# calculator4.net
KiCad netlist of a schematic drawn in EAGLE
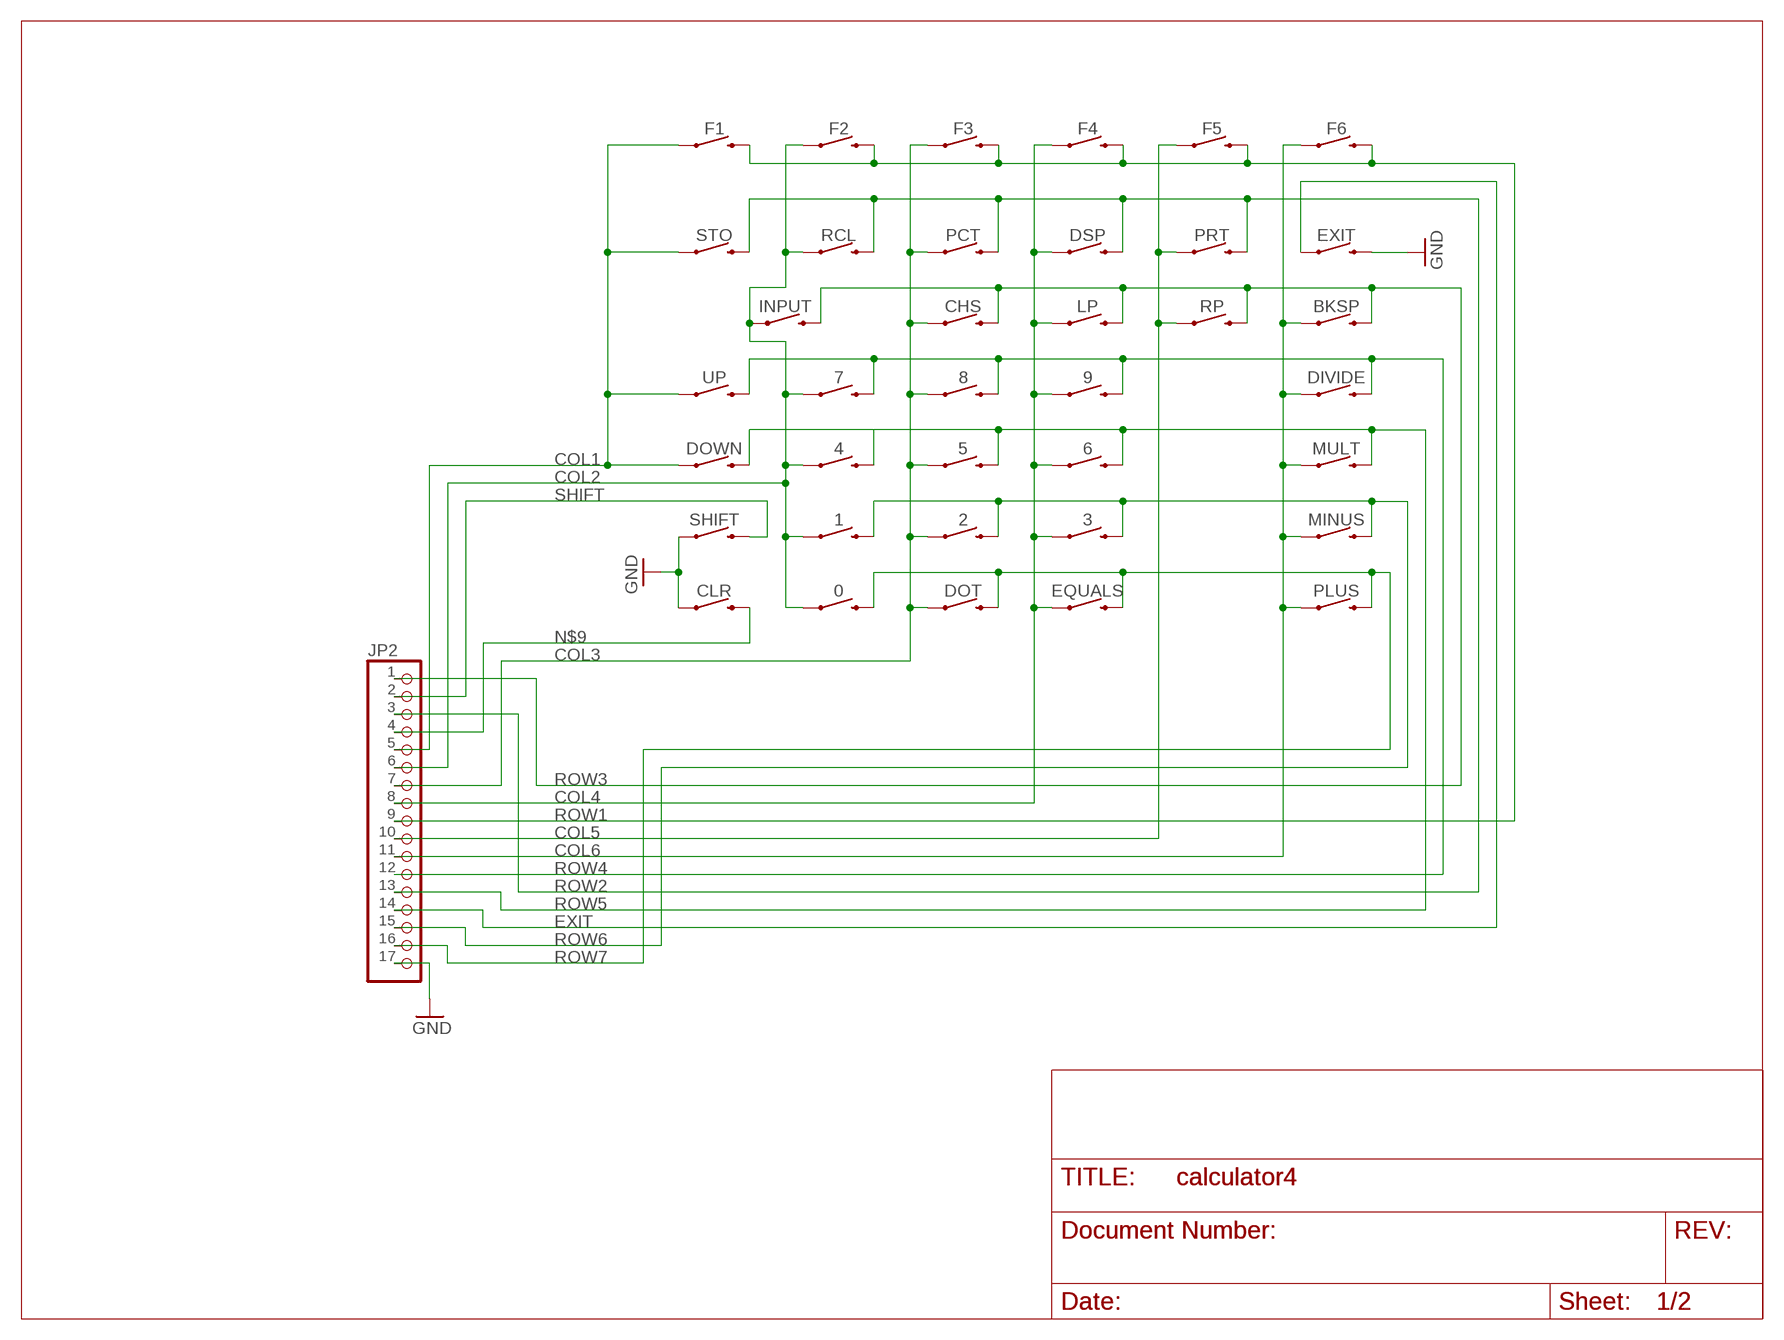
[diagram p0: schematic, sheet 1]
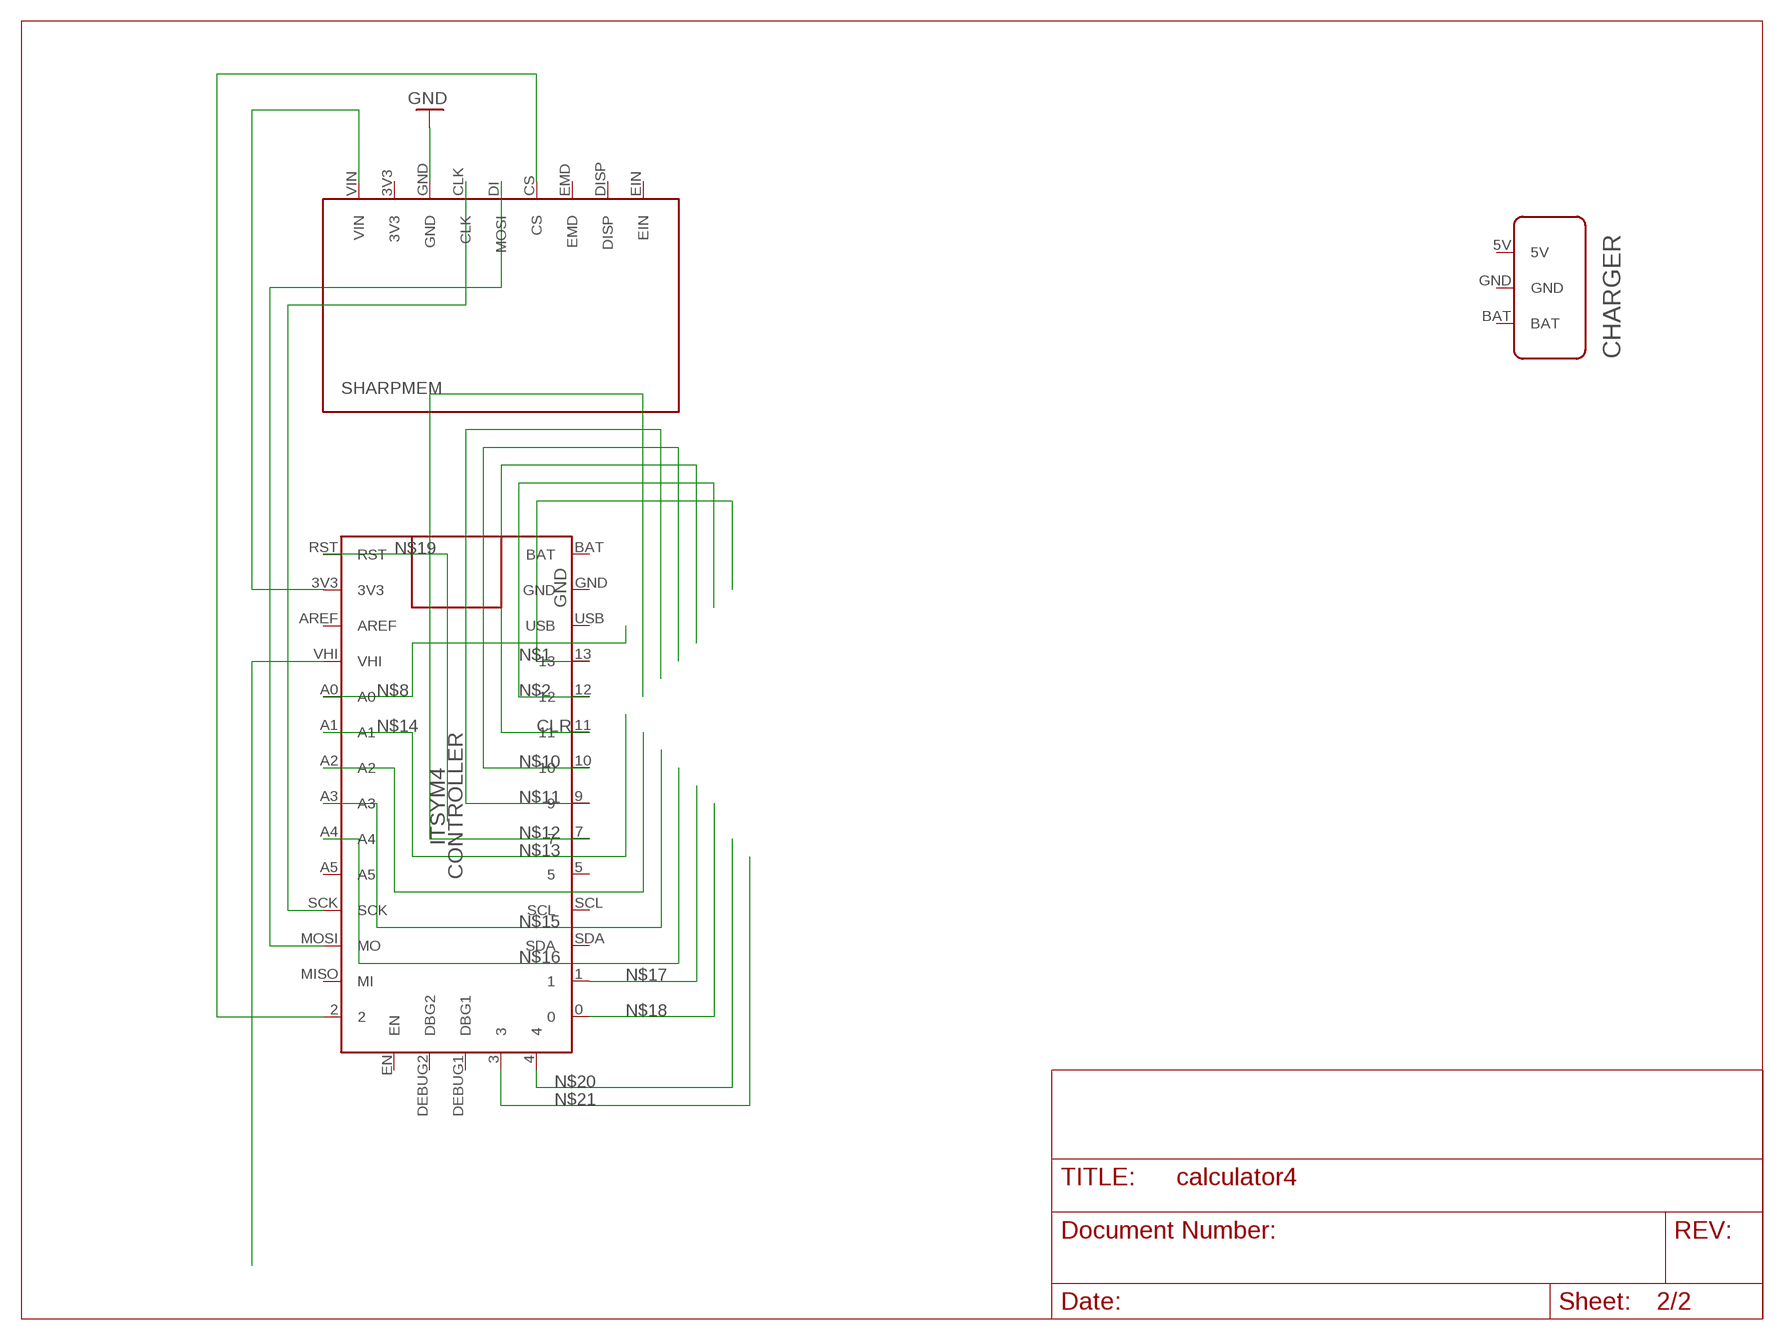
[diagram p1: schematic, sheet 2]

(export (version "E")
  (design (tool "Eeschema 10.0.6"))
  (components
    (comp (ref "0")
      (value "BUTTON")
      (footprint "eagle-import:BUTTON")
      (libsource (lib "eagle-import") (part "BUTTON"))
    )
    (comp (ref "1")
      (value "BUTTON")
      (footprint "eagle-import:BUTTON")
      (libsource (lib "eagle-import") (part "BUTTON"))
    )
    (comp (ref "2")
      (value "BUTTON")
      (footprint "eagle-import:BUTTON")
      (libsource (lib "eagle-import") (part "BUTTON"))
    )
    (comp (ref "3")
      (value "BUTTON")
      (footprint "eagle-import:BUTTON")
      (libsource (lib "eagle-import") (part "BUTTON"))
    )
    (comp (ref "4")
      (value "BUTTON")
      (footprint "eagle-import:BUTTON")
      (libsource (lib "eagle-import") (part "BUTTON"))
    )
    (comp (ref "5")
      (value "BUTTON")
      (footprint "eagle-import:BUTTON")
      (libsource (lib "eagle-import") (part "BUTTON"))
    )
    (comp (ref "6")
      (value "BUTTON")
      (footprint "eagle-import:BUTTON")
      (libsource (lib "eagle-import") (part "BUTTON"))
    )
    (comp (ref "7")
      (value "BUTTON")
      (footprint "eagle-import:BUTTON")
      (libsource (lib "eagle-import") (part "BUTTON"))
    )
    (comp (ref "8")
      (value "BUTTON")
      (footprint "eagle-import:BUTTON")
      (libsource (lib "eagle-import") (part "BUTTON"))
    )
    (comp (ref "9")
      (value "BUTTON")
      (footprint "eagle-import:BUTTON")
      (libsource (lib "eagle-import") (part "BUTTON"))
    )
    (comp (ref "BKSP")
      (value "BUTTON")
      (footprint "eagle-import:BUTTON")
      (libsource (lib "eagle-import") (part "BUTTON"))
    )
    (comp (ref "CHS")
      (value "BUTTON")
      (footprint "eagle-import:BUTTON")
      (libsource (lib "eagle-import") (part "BUTTON"))
    )
    (comp (ref "CLR")
      (value "BUTTON")
      (footprint "eagle-import:BUTTON")
      (libsource (lib "eagle-import") (part "BUTTON"))
    )
    (comp (ref "DIVIDE")
      (value "BUTTON")
      (footprint "eagle-import:BUTTON")
      (libsource (lib "eagle-import") (part "BUTTON"))
    )
    (comp (ref "DOT")
      (value "BUTTON")
      (footprint "eagle-import:BUTTON")
      (libsource (lib "eagle-import") (part "BUTTON"))
    )
    (comp (ref "DOWN")
      (value "BUTTON")
      (footprint "eagle-import:BUTTON")
      (libsource (lib "eagle-import") (part "BUTTON"))
    )
    (comp (ref "DSP")
      (value "BUTTON")
      (footprint "eagle-import:BUTTON")
      (libsource (lib "eagle-import") (part "BUTTON"))
    )
    (comp (ref "EQUALS")
      (value "BUTTON")
      (footprint "eagle-import:BUTTON")
      (libsource (lib "eagle-import") (part "BUTTON"))
    )
    (comp (ref "EXIT")
      (value "BUTTON")
      (footprint "eagle-import:BUTTON")
      (libsource (lib "eagle-import") (part "BUTTON"))
    )
    (comp (ref "F1")
      (value "BUTTON")
      (footprint "eagle-import:BUTTON")
      (libsource (lib "eagle-import") (part "BUTTON"))
    )
    (comp (ref "F2")
      (value "BUTTON")
      (footprint "eagle-import:BUTTON")
      (libsource (lib "eagle-import") (part "BUTTON"))
    )
    (comp (ref "F3")
      (value "BUTTON")
      (footprint "eagle-import:BUTTON")
      (libsource (lib "eagle-import") (part "BUTTON"))
    )
    (comp (ref "F4")
      (value "BUTTON")
      (footprint "eagle-import:BUTTON")
      (libsource (lib "eagle-import") (part "BUTTON"))
    )
    (comp (ref "F5")
      (value "BUTTON")
      (footprint "eagle-import:BUTTON")
      (libsource (lib "eagle-import") (part "BUTTON"))
    )
    (comp (ref "F6")
      (value "BUTTON")
      (footprint "eagle-import:BUTTON")
      (libsource (lib "eagle-import") (part "BUTTON"))
    )
    (comp (ref "INPUT")
      (value "BUTTON")
      (footprint "eagle-import:BUTTON")
      (libsource (lib "eagle-import") (part "BUTTON"))
    )
    (comp (ref "JP2")
      (value "PINHD-1X17/90")
      (footprint "eagle-import:1X17_90")
      (libsource (lib "eagle-import") (part "PINHD-1X17/90"))
    )
    (comp (ref "LP")
      (value "BUTTON")
      (footprint "eagle-import:BUTTON")
      (libsource (lib "eagle-import") (part "BUTTON"))
    )
    (comp (ref "MINUS")
      (value "BUTTON")
      (footprint "eagle-import:BUTTON")
      (libsource (lib "eagle-import") (part "BUTTON"))
    )
    (comp (ref "MULT")
      (value "BUTTON")
      (footprint "eagle-import:BUTTON")
      (libsource (lib "eagle-import") (part "BUTTON"))
    )
    (comp (ref "PCT")
      (value "BUTTON")
      (footprint "eagle-import:BUTTON")
      (libsource (lib "eagle-import") (part "BUTTON"))
    )
    (comp (ref "PLUS")
      (value "BUTTON")
      (footprint "eagle-import:BUTTON")
      (libsource (lib "eagle-import") (part "BUTTON"))
    )
    (comp (ref "PRT")
      (value "BUTTON")
      (footprint "eagle-import:BUTTON")
      (libsource (lib "eagle-import") (part "BUTTON"))
    )
    (comp (ref "RCL")
      (value "BUTTON")
      (footprint "eagle-import:BUTTON")
      (libsource (lib "eagle-import") (part "BUTTON"))
    )
    (comp (ref "RP")
      (value "BUTTON")
      (footprint "eagle-import:BUTTON")
      (libsource (lib "eagle-import") (part "BUTTON"))
    )
    (comp (ref "SHIFT")
      (value "BUTTON")
      (footprint "eagle-import:BUTTON")
      (libsource (lib "eagle-import") (part "BUTTON"))
    )
    (comp (ref "STO")
      (value "BUTTON")
      (footprint "eagle-import:BUTTON")
      (libsource (lib "eagle-import") (part "BUTTON"))
    )
    (comp (ref "UP")
      (value "BUTTON")
      (footprint "eagle-import:BUTTON")
      (libsource (lib "eagle-import") (part "BUTTON"))
    )
    (comp (ref "CHARGER")
      (value "LIPO_BACKPACK")
      (footprint "eagle-import:LIPO_BACKPACK")
      (libsource (lib "eagle-import") (part "LIPO_BACKPACK"))
    )
    (comp (ref "CONTROLLER")
      (value "ITSYM4")
      (footprint "eagle-import:ITSYM4")
      (libsource (lib "eagle-import") (part "ITSYM4"))
    )
    (comp (ref "SHARPMEM")
      (value "SHARPMEM")
      (footprint "eagle-import:SHARPMEM")
      (libsource (lib "eagle-import") (part "SHARPMEM"))
    )
  )
  (nets
    (net (code "1") (name "CLR") (class "Default")
      (node (ref "CONTROLLER") (pin "11") (pinfunction "11_11") (pintype "bidirectional"))
    )
    (net (code "2") (name "COL1") (class "Default")
      (node (ref "DOWN") (pin "1") (pinfunction "1_1") (pintype "passive"))
      (node (ref "F1") (pin "1") (pinfunction "1_1") (pintype "passive"))
      (node (ref "JP2") (pin "5") (pinfunction "5_5") (pintype "passive"))
      (node (ref "STO") (pin "1") (pinfunction "1_1") (pintype "passive"))
      (node (ref "UP") (pin "1") (pinfunction "1_1") (pintype "passive"))
    )
    (net (code "3") (name "COL2") (class "Default")
      (node (ref "0") (pin "1") (pinfunction "1_1") (pintype "passive"))
      (node (ref "1") (pin "1") (pinfunction "1_1") (pintype "passive"))
      (node (ref "4") (pin "1") (pinfunction "1_1") (pintype "passive"))
      (node (ref "7") (pin "1") (pinfunction "1_1") (pintype "passive"))
      (node (ref "F2") (pin "1") (pinfunction "1_1") (pintype "passive"))
      (node (ref "INPUT") (pin "1") (pinfunction "1_1") (pintype "passive"))
      (node (ref "JP2") (pin "6") (pinfunction "6_6") (pintype "passive"))
      (node (ref "RCL") (pin "1") (pinfunction "1_1") (pintype "passive"))
    )
    (net (code "4") (name "COL3") (class "Default")
      (node (ref "2") (pin "1") (pinfunction "1_1") (pintype "passive"))
      (node (ref "5") (pin "1") (pinfunction "1_1") (pintype "passive"))
      (node (ref "8") (pin "1") (pinfunction "1_1") (pintype "passive"))
      (node (ref "CHS") (pin "1") (pinfunction "1_1") (pintype "passive"))
      (node (ref "DOT") (pin "1") (pinfunction "1_1") (pintype "passive"))
      (node (ref "F3") (pin "1") (pinfunction "1_1") (pintype "passive"))
      (node (ref "JP2") (pin "7") (pinfunction "7_7") (pintype "passive"))
      (node (ref "PCT") (pin "1") (pinfunction "1_1") (pintype "passive"))
    )
    (net (code "5") (name "COL4") (class "Default")
      (node (ref "3") (pin "1") (pinfunction "1_1") (pintype "passive"))
      (node (ref "6") (pin "1") (pinfunction "1_1") (pintype "passive"))
      (node (ref "9") (pin "1") (pinfunction "1_1") (pintype "passive"))
      (node (ref "DSP") (pin "1") (pinfunction "1_1") (pintype "passive"))
      (node (ref "EQUALS") (pin "1") (pinfunction "1_1") (pintype "passive"))
      (node (ref "F4") (pin "1") (pinfunction "1_1") (pintype "passive"))
      (node (ref "JP2") (pin "8") (pinfunction "8_8") (pintype "passive"))
      (node (ref "LP") (pin "1") (pinfunction "1_1") (pintype "passive"))
    )
    (net (code "6") (name "COL5") (class "Default")
      (node (ref "F5") (pin "1") (pinfunction "1_1") (pintype "passive"))
      (node (ref "JP2") (pin "10") (pinfunction "10_10") (pintype "passive"))
      (node (ref "PRT") (pin "1") (pinfunction "1_1") (pintype "passive"))
      (node (ref "RP") (pin "1") (pinfunction "1_1") (pintype "passive"))
    )
    (net (code "7") (name "COL6") (class "Default")
      (node (ref "BKSP") (pin "1") (pinfunction "1_1") (pintype "passive"))
      (node (ref "DIVIDE") (pin "1") (pinfunction "1_1") (pintype "passive"))
      (node (ref "F6") (pin "1") (pinfunction "1_1") (pintype "passive"))
      (node (ref "JP2") (pin "11") (pinfunction "11_11") (pintype "passive"))
      (node (ref "MINUS") (pin "1") (pinfunction "1_1") (pintype "passive"))
      (node (ref "MULT") (pin "1") (pinfunction "1_1") (pintype "passive"))
      (node (ref "PLUS") (pin "1") (pinfunction "1_1") (pintype "passive"))
    )
    (net (code "8") (name "EXIT") (class "Default")
      (node (ref "EXIT") (pin "1") (pinfunction "1_1") (pintype "passive"))
      (node (ref "JP2") (pin "14") (pinfunction "14_14") (pintype "passive"))
    )
    (net (code "9") (name "GND") (class "Default")
      (node (ref "CLR") (pin "1") (pinfunction "1_1") (pintype "passive"))
      (node (ref "CONTROLLER") (pin "GND") (pinfunction "GND_GND") (pintype "bidirectional"))
      (node (ref "EXIT") (pin "3") (pinfunction "2_3") (pintype "passive"))
      (node (ref "JP2") (pin "17") (pinfunction "17_17") (pintype "passive"))
      (node (ref "SHARPMEM") (pin "GND") (pinfunction "GND_GND") (pintype "bidirectional"))
      (node (ref "SHIFT") (pin "1") (pinfunction "1_1") (pintype "passive"))
    )
    (net (code "10") (name "N$1") (class "Default")
      (node (ref "CONTROLLER") (pin "13") (pinfunction "13_13") (pintype "bidirectional"))
    )
    (net (code "11") (name "N$2") (class "Default")
      (node (ref "CONTROLLER") (pin "12") (pinfunction "12_12") (pintype "bidirectional"))
    )
    (net (code "12") (name "N$8") (class "Default")
      (node (ref "CONTROLLER") (pin "A0") (pinfunction "A0_A0") (pintype "bidirectional"))
    )
    (net (code "13") (name "N$9") (class "Default")
      (node (ref "CLR") (pin "3") (pinfunction "2_3") (pintype "passive"))
      (node (ref "JP2") (pin "4") (pinfunction "4_4") (pintype "passive"))
    )
    (net (code "14") (name "N$10") (class "Default")
      (node (ref "CONTROLLER") (pin "10") (pinfunction "10_10") (pintype "bidirectional"))
    )
    (net (code "15") (name "N$11") (class "Default")
      (node (ref "CONTROLLER") (pin "9") (pinfunction "9_9") (pintype "bidirectional"))
    )
    (net (code "16") (name "N$12") (class "Default")
      (node (ref "CONTROLLER") (pin "7") (pinfunction "7_7") (pintype "bidirectional"))
    )
    (net (code "17") (name "N$13") (class "Default")
      (node (ref "CONTROLLER") (pin "A1") (pinfunction "A1_A1") (pintype "bidirectional"))
    )
    (net (code "18") (name "N$14") (class "Default")
      (node (ref "CONTROLLER") (pin "A2") (pinfunction "A2_A2") (pintype "bidirectional"))
    )
    (net (code "19") (name "N$15") (class "Default")
      (node (ref "CONTROLLER") (pin "A3") (pinfunction "A3_A3") (pintype "bidirectional"))
    )
    (net (code "20") (name "N$16") (class "Default")
      (node (ref "CONTROLLER") (pin "A4") (pinfunction "A4_A4") (pintype "bidirectional"))
    )
    (net (code "21") (name "N$17") (class "Default")
      (node (ref "CONTROLLER") (pin "1") (pinfunction "1_1") (pintype "bidirectional"))
    )
    (net (code "22") (name "N$18") (class "Default")
      (node (ref "CONTROLLER") (pin "0") (pinfunction "0_0") (pintype "bidirectional"))
    )
    (net (code "23") (name "N$19") (class "Default")
      (node (ref "CONTROLLER") (pin "RST") (pinfunction "RST_RST") (pintype "bidirectional"))
    )
    (net (code "24") (name "N$20") (class "Default")
      (node (ref "CONTROLLER") (pin "4") (pinfunction "4_4") (pintype "bidirectional"))
    )
    (net (code "25") (name "N$21") (class "Default")
      (node (ref "CONTROLLER") (pin "3") (pinfunction "3_3") (pintype "bidirectional"))
    )
    (net (code "26") (name "Net-(CONTROLLER-MO)") (class "Default")
      (node (ref "CONTROLLER") (pin "MOSI") (pinfunction "MO_MOSI") (pintype "bidirectional"))
      (node (ref "SHARPMEM") (pin "DI") (pinfunction "MOSI_DI") (pintype "bidirectional"))
    )
    (net (code "27") (name "Net-(CONTROLLER-Pad2)") (class "Default")
      (node (ref "CONTROLLER") (pin "2") (pinfunction "2_2") (pintype "bidirectional"))
      (node (ref "SHARPMEM") (pin "CS") (pinfunction "CS_CS") (pintype "bidirectional"))
    )
    (net (code "28") (name "Net-(CONTROLLER-Pad3V3)") (class "Default")
      (node (ref "CONTROLLER") (pin "3V3") (pinfunction "3V3_3V3") (pintype "bidirectional"))
      (node (ref "SHARPMEM") (pin "VIN") (pinfunction "VIN_VIN") (pintype "bidirectional"))
    )
    (net (code "29") (name "Net-(CONTROLLER-PadSCK)") (class "Default")
      (node (ref "CONTROLLER") (pin "SCK") (pinfunction "SCK_SCK") (pintype "bidirectional"))
      (node (ref "SHARPMEM") (pin "CLK") (pinfunction "CLK_CLK") (pintype "bidirectional"))
    )
    (net (code "30") (name "ROW1") (class "Default")
      (node (ref "F1") (pin "3") (pinfunction "2_3") (pintype "passive"))
      (node (ref "F2") (pin "3") (pinfunction "2_3") (pintype "passive"))
      (node (ref "F3") (pin "3") (pinfunction "2_3") (pintype "passive"))
      (node (ref "F4") (pin "3") (pinfunction "2_3") (pintype "passive"))
      (node (ref "F5") (pin "3") (pinfunction "2_3") (pintype "passive"))
      (node (ref "F6") (pin "3") (pinfunction "2_3") (pintype "passive"))
      (node (ref "JP2") (pin "9") (pinfunction "9_9") (pintype "passive"))
    )
    (net (code "31") (name "ROW2") (class "Default")
      (node (ref "DSP") (pin "3") (pinfunction "2_3") (pintype "passive"))
      (node (ref "JP2") (pin "3") (pinfunction "3_3") (pintype "passive"))
      (node (ref "PCT") (pin "3") (pinfunction "2_3") (pintype "passive"))
      (node (ref "PRT") (pin "3") (pinfunction "2_3") (pintype "passive"))
      (node (ref "RCL") (pin "3") (pinfunction "2_3") (pintype "passive"))
      (node (ref "STO") (pin "3") (pinfunction "2_3") (pintype "passive"))
    )
    (net (code "32") (name "ROW3") (class "Default")
      (node (ref "BKSP") (pin "3") (pinfunction "2_3") (pintype "passive"))
      (node (ref "CHS") (pin "3") (pinfunction "2_3") (pintype "passive"))
      (node (ref "INPUT") (pin "3") (pinfunction "2_3") (pintype "passive"))
      (node (ref "JP2") (pin "1") (pinfunction "1_1") (pintype "passive"))
      (node (ref "LP") (pin "3") (pinfunction "2_3") (pintype "passive"))
      (node (ref "RP") (pin "3") (pinfunction "2_3") (pintype "passive"))
    )
    (net (code "33") (name "ROW4") (class "Default")
      (node (ref "7") (pin "3") (pinfunction "2_3") (pintype "passive"))
      (node (ref "8") (pin "3") (pinfunction "2_3") (pintype "passive"))
      (node (ref "9") (pin "3") (pinfunction "2_3") (pintype "passive"))
      (node (ref "DIVIDE") (pin "3") (pinfunction "2_3") (pintype "passive"))
      (node (ref "JP2") (pin "12") (pinfunction "12_12") (pintype "passive"))
      (node (ref "UP") (pin "3") (pinfunction "2_3") (pintype "passive"))
    )
    (net (code "34") (name "ROW5") (class "Default")
      (node (ref "4") (pin "3") (pinfunction "2_3") (pintype "passive"))
      (node (ref "5") (pin "3") (pinfunction "2_3") (pintype "passive"))
      (node (ref "6") (pin "3") (pinfunction "2_3") (pintype "passive"))
      (node (ref "DOWN") (pin "3") (pinfunction "2_3") (pintype "passive"))
      (node (ref "JP2") (pin "13") (pinfunction "13_13") (pintype "passive"))
      (node (ref "MULT") (pin "3") (pinfunction "2_3") (pintype "passive"))
    )
    (net (code "35") (name "ROW6") (class "Default")
      (node (ref "1") (pin "3") (pinfunction "2_3") (pintype "passive"))
      (node (ref "2") (pin "3") (pinfunction "2_3") (pintype "passive"))
      (node (ref "3") (pin "3") (pinfunction "2_3") (pintype "passive"))
      (node (ref "JP2") (pin "15") (pinfunction "15_15") (pintype "passive"))
      (node (ref "MINUS") (pin "3") (pinfunction "2_3") (pintype "passive"))
    )
    (net (code "36") (name "ROW7") (class "Default")
      (node (ref "0") (pin "3") (pinfunction "2_3") (pintype "passive"))
      (node (ref "DOT") (pin "3") (pinfunction "2_3") (pintype "passive"))
      (node (ref "EQUALS") (pin "3") (pinfunction "2_3") (pintype "passive"))
      (node (ref "JP2") (pin "16") (pinfunction "16_16") (pintype "passive"))
      (node (ref "PLUS") (pin "3") (pinfunction "2_3") (pintype "passive"))
    )
    (net (code "37") (name "SHIFT") (class "Default")
      (node (ref "JP2") (pin "2") (pinfunction "2_2") (pintype "passive"))
      (node (ref "SHIFT") (pin "3") (pinfunction "2_3") (pintype "passive"))
    )
    (net (code "38") (name "unconnected-(CHARGER-Pad5V)") (class "Default")
      (node (ref "CHARGER") (pin "5V") (pinfunction "5V_5V") (pintype "bidirectional"))
    )
    (net (code "39") (name "unconnected-(CHARGER-PadBAT)") (class "Default")
      (node (ref "CHARGER") (pin "BAT") (pinfunction "BAT_BAT") (pintype "bidirectional"))
    )
    (net (code "40") (name "unconnected-(CHARGER-PadGND)") (class "Default")
      (node (ref "CHARGER") (pin "GND") (pinfunction "GND_GND") (pintype "bidirectional"))
    )
    (net (code "41") (name "unconnected-(CONTROLLER-DBG1-PadDEBUG1)") (class "Default")
      (node (ref "CONTROLLER") (pin "DEBUG1") (pinfunction "DBG1_DEBUG1") (pintype "bidirectional"))
    )
    (net (code "42") (name "unconnected-(CONTROLLER-DBG2-PadDEBUG2)") (class "Default")
      (node (ref "CONTROLLER") (pin "DEBUG2") (pinfunction "DBG2_DEBUG2") (pintype "bidirectional"))
    )
    (net (code "43") (name "unconnected-(CONTROLLER-MI-PadMISO)") (class "Default")
      (node (ref "CONTROLLER") (pin "MISO") (pinfunction "MI_MISO") (pintype "bidirectional"))
    )
    (net (code "44") (name "unconnected-(CONTROLLER-Pad5)") (class "Default")
      (node (ref "CONTROLLER") (pin "5") (pinfunction "5_5") (pintype "bidirectional"))
    )
    (net (code "45") (name "unconnected-(CONTROLLER-PadA5)") (class "Default")
      (node (ref "CONTROLLER") (pin "A5") (pinfunction "A5_A5") (pintype "bidirectional"))
    )
    (net (code "46") (name "unconnected-(CONTROLLER-PadAREF)") (class "Default")
      (node (ref "CONTROLLER") (pin "AREF") (pinfunction "AREF_AREF") (pintype "bidirectional"))
    )
    (net (code "47") (name "unconnected-(CONTROLLER-PadBAT)") (class "Default")
      (node (ref "CONTROLLER") (pin "BAT") (pinfunction "BAT_BAT") (pintype "bidirectional"))
    )
    (net (code "48") (name "unconnected-(CONTROLLER-PadEN)") (class "Default")
      (node (ref "CONTROLLER") (pin "EN") (pinfunction "EN_EN") (pintype "bidirectional"))
    )
    (net (code "49") (name "unconnected-(CONTROLLER-PadSCL)") (class "Default")
      (node (ref "CONTROLLER") (pin "SCL") (pinfunction "SCL_SCL") (pintype "bidirectional"))
    )
    (net (code "50") (name "unconnected-(CONTROLLER-PadSDA)") (class "Default")
      (node (ref "CONTROLLER") (pin "SDA") (pinfunction "SDA_SDA") (pintype "bidirectional"))
    )
    (net (code "51") (name "unconnected-(CONTROLLER-PadUSB)") (class "Default")
      (node (ref "CONTROLLER") (pin "USB") (pinfunction "USB_USB") (pintype "bidirectional"))
    )
    (net (code "52") (name "unconnected-(CONTROLLER-PadVHI)") (class "Default")
      (node (ref "CONTROLLER") (pin "VHI") (pinfunction "VHI_VHI") (pintype "bidirectional"))
    )
    (net (code "53") (name "unconnected-(SHARPMEM-Pad3V3)") (class "Default")
      (node (ref "SHARPMEM") (pin "3V3") (pinfunction "3V3_3V3") (pintype "bidirectional"))
    )
    (net (code "54") (name "unconnected-(SHARPMEM-PadDISP)") (class "Default")
      (node (ref "SHARPMEM") (pin "DISP") (pinfunction "DISP_DISP") (pintype "bidirectional"))
    )
    (net (code "55") (name "unconnected-(SHARPMEM-PadEIN)") (class "Default")
      (node (ref "SHARPMEM") (pin "EIN") (pinfunction "EIN_EIN") (pintype "bidirectional"))
    )
    (net (code "56") (name "unconnected-(SHARPMEM-PadEMD)") (class "Default")
      (node (ref "SHARPMEM") (pin "EMD") (pinfunction "EMD_EMD") (pintype "bidirectional"))
    )
  )
)
